# working.net
KiCad netlist of a schematic drawn in EAGLE
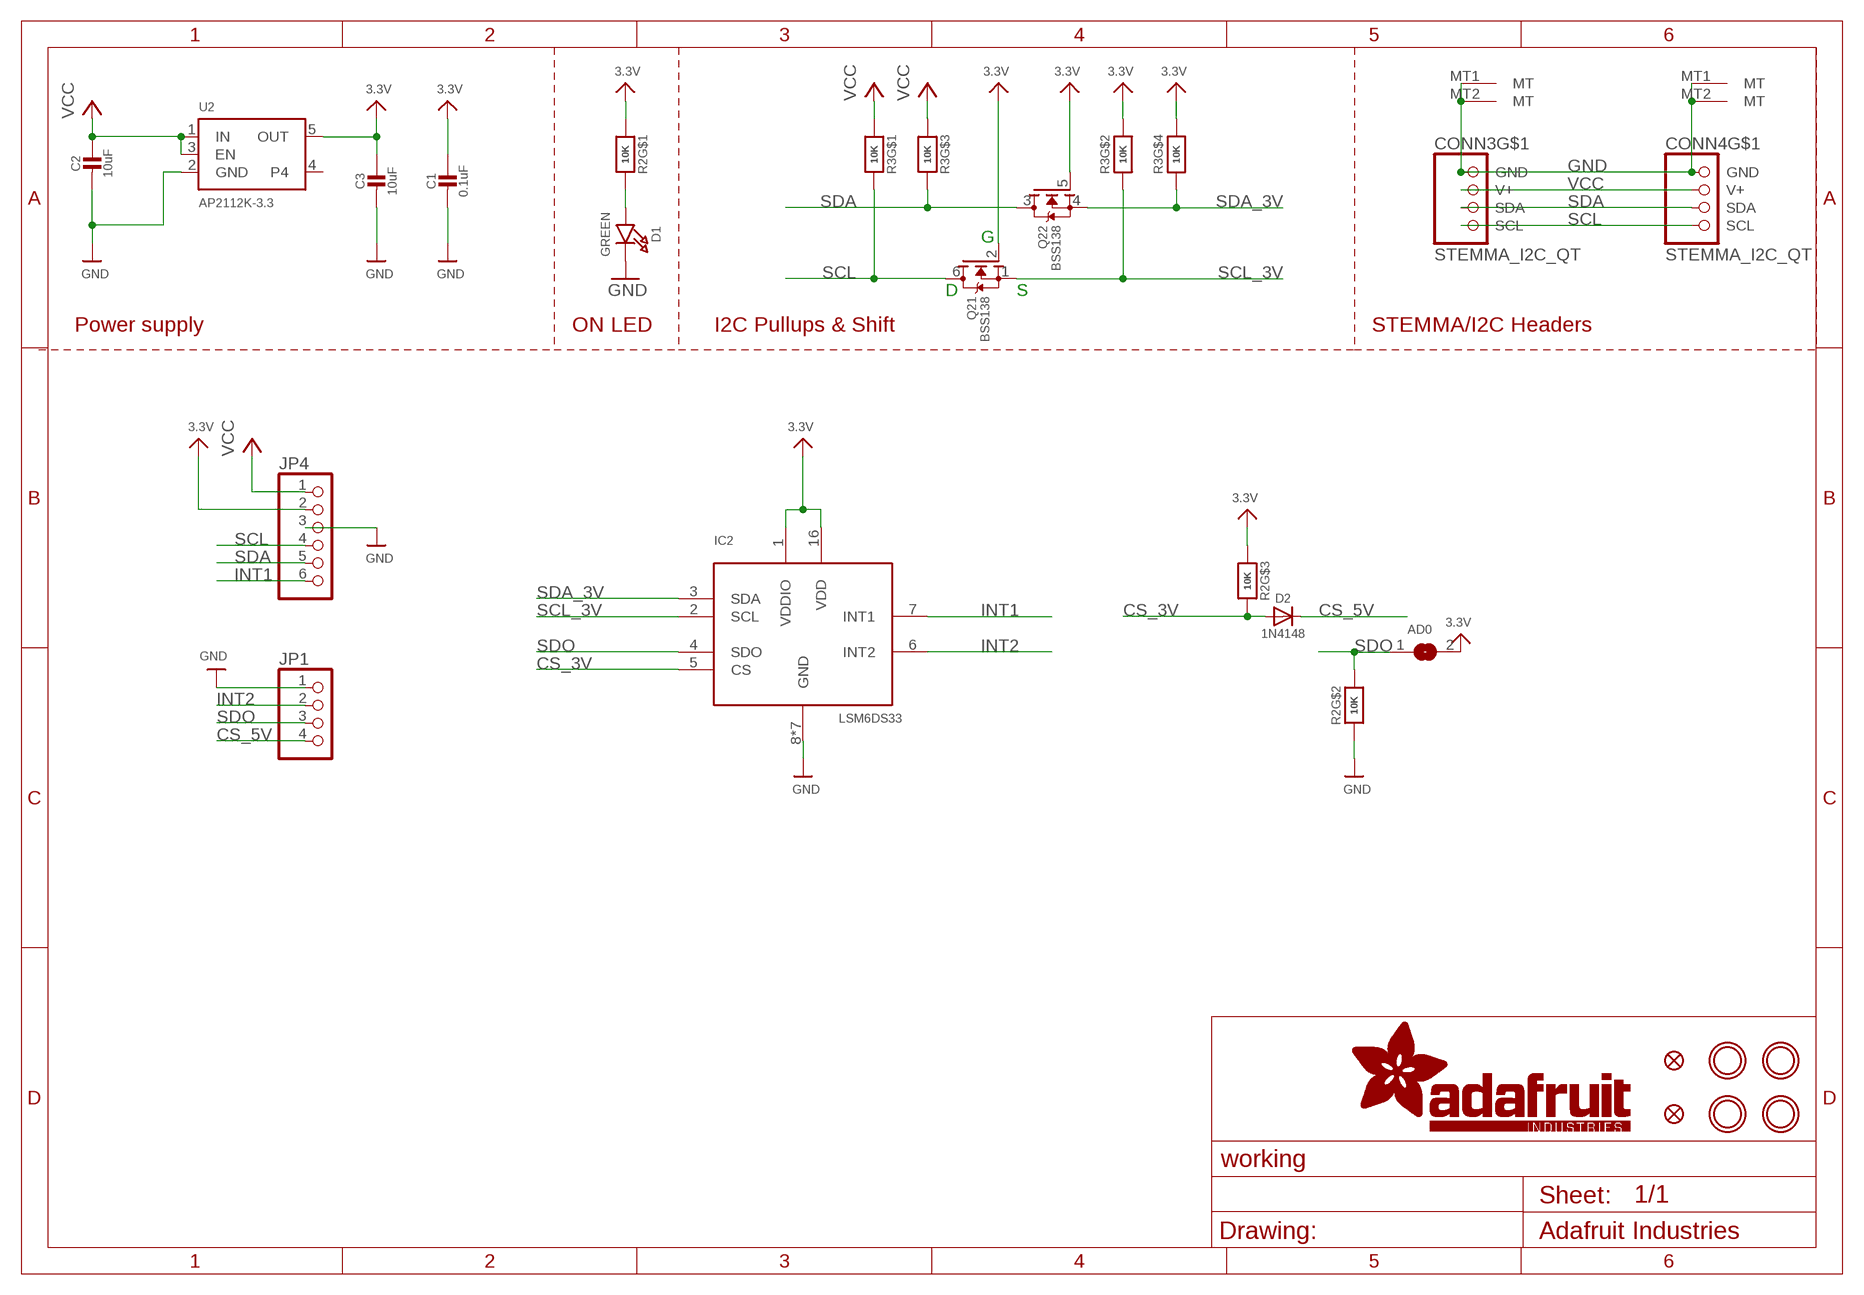
[diagram p0: schematic, sheet 1]

(export (version "E")
  (design (tool "Eeschema 10.0.6"))
  (components
    (comp (ref "AD0")
      (value "SOLDERJUMPER")
      (footprint "eagle-import:SOLDERJUMPER_ARROW_NOPASTE")
      (libsource (lib "eagle-import") (part "SOLDERJUMPER"))
    )
    (comp (ref "C1")
      (value "0.1uF")
      (footprint "eagle-import:0603-NO")
      (libsource (lib "eagle-import") (part "CAP_CERAMIC0603_NO"))
    )
    (comp (ref "C2")
      (value "10uF")
      (footprint "eagle-import:0805-NO")
      (libsource (lib "eagle-import") (part "CAP_CERAMIC0805-NOOUTLINE"))
    )
    (comp (ref "C3")
      (value "10uF")
      (footprint "eagle-import:0805-NO")
      (libsource (lib "eagle-import") (part "CAP_CERAMIC0805-NOOUTLINE"))
    )
    (comp (ref "CONN3")
      (value "STEMMA_I2C_QT")
      (footprint "eagle-import:JST_SH4")
      (libsource (lib "eagle-import") (part "STEMMA_I2C_QT"))
    )
    (comp (ref "CONN4")
      (value "STEMMA_I2C_QT")
      (footprint "eagle-import:JST_SH4")
      (libsource (lib "eagle-import") (part "STEMMA_I2C_QT"))
    )
    (comp (ref "D1")
      (value "GREEN")
      (footprint "eagle-import:CHIPLED_0603_NOOUTLINE")
      (libsource (lib "eagle-import") (part "LED0603_NOOUTLINE"))
    )
    (comp (ref "D2")
      (value "1N4148")
      (footprint "eagle-import:SOD-323")
      (libsource (lib "eagle-import") (part "DIODESOD-323"))
    )
    (comp (ref "FID3")
      (value "FIDUCIAL_1MM")
      (footprint "eagle-import:FIDUCIAL_1MM")
      (libsource (lib "eagle-import") (part "FIDUCIAL_1MM"))
    )
    (comp (ref "FID4")
      (value "FIDUCIAL_1MM")
      (footprint "eagle-import:FIDUCIAL_1MM")
      (libsource (lib "eagle-import") (part "FIDUCIAL_1MM"))
    )
    (comp (ref "IC2")
      (value "LSM6DS33")
      (footprint "eagle-import:LGA16_3X3MM")
      (libsource (lib "eagle-import") (part "LSM6DS33"))
    )
    (comp (ref "JP1")
      (value "HEADER-1X4ROUND")
      (footprint "eagle-import:1X04_ROUND")
      (libsource (lib "eagle-import") (part "HEADER-1X4ROUND"))
    )
    (comp (ref "JP4")
      (value "HEADER-1X670MIL")
      (footprint "eagle-import:1X06_ROUND_70")
      (libsource (lib "eagle-import") (part "HEADER-1X670MIL"))
    )
    (comp (ref "Q2")
      (value "BSS138")
      (footprint "eagle-import:SOT363")
      (libsource (lib "eagle-import") (part "MOSFET-N_DUAL"))
    )
    (comp (ref "R2")
      (value "10K")
      (footprint "eagle-import:RESPACK_4X0603")
      (libsource (lib "eagle-import") (part "RESISTOR_4PACK"))
    )
    (comp (ref "R3")
      (value "10K")
      (footprint "eagle-import:RESPACK_4X0603")
      (libsource (lib "eagle-import") (part "RESISTOR_4PACK"))
    )
    (comp (ref "U$1")
      (value "MOUNTINGHOLE2.5")
      (footprint "eagle-import:MOUNTINGHOLE_2.5_PLATED")
      (libsource (lib "eagle-import") (part "MOUNTINGHOLE2.5"))
    )
    (comp (ref "U$17")
      (value "MOUNTINGHOLE2.5")
      (footprint "eagle-import:MOUNTINGHOLE_2.5_PLATED")
      (libsource (lib "eagle-import") (part "MOUNTINGHOLE2.5"))
    )
    (comp (ref "U$19")
      (value "MOUNTINGHOLE2.5")
      (footprint "eagle-import:MOUNTINGHOLE_2.5_PLATED")
      (libsource (lib "eagle-import") (part "MOUNTINGHOLE2.5"))
    )
    (comp (ref "U$21")
      (value "MOUNTINGHOLE2.5")
      (footprint "eagle-import:MOUNTINGHOLE_2.5_PLATED")
      (libsource (lib "eagle-import") (part "MOUNTINGHOLE2.5"))
    )
    (comp (ref "U2")
      (value "AP2112K-3.3")
      (footprint "eagle-import:SOT23-5")
      (libsource (lib "eagle-import") (part "VREG_SOT23-5"))
    )
  )
  (nets
    (net (code "1") (name "/CS_3V") (class "Default")
      (node (ref "D2") (pin "A") (pinfunction "A_A") (pintype "passive"))
      (node (ref "IC2") (pin "5") (pinfunction "CS_5") (pintype "input"))
      (node (ref "R2") (pin "6") (pinfunction "2_6") (pintype "passive"))
    )
    (net (code "2") (name "/CS_5V") (class "Default")
      (node (ref "D2") (pin "C") (pinfunction "C_C") (pintype "passive"))
      (node (ref "JP1") (pin "4") (pinfunction "4_4") (pintype "passive"))
    )
    (net (code "3") (name "/INT1") (class "Default")
      (node (ref "IC2") (pin "7") (pinfunction "INT1_7") (pintype "output"))
      (node (ref "JP4") (pin "6") (pinfunction "6_6") (pintype "passive"))
    )
    (net (code "4") (name "/INT2") (class "Default")
      (node (ref "IC2") (pin "6") (pinfunction "INT2_6") (pintype "output"))
      (node (ref "JP1") (pin "2") (pinfunction "2_2") (pintype "passive"))
    )
    (net (code "5") (name "/SCL") (class "Default")
      (node (ref "CONN3") (pin "4") (pinfunction "SCL_4") (pintype "passive"))
      (node (ref "CONN4") (pin "4") (pinfunction "SCL_4") (pintype "passive"))
      (node (ref "JP4") (pin "4") (pinfunction "4_4") (pintype "passive"))
      (node (ref "Q2") (pin "6") (pinfunction "D_6") (pintype "bidirectional"))
      (node (ref "R3") (pin "8") (pinfunction "2_8") (pintype "passive"))
    )
    (net (code "6") (name "/SCL_3V") (class "Default")
      (node (ref "IC2") (pin "2") (pinfunction "SCL_2") (pintype "bidirectional"))
      (node (ref "Q2") (pin "1") (pinfunction "S_1") (pintype "bidirectional"))
      (node (ref "R3") (pin "7") (pinfunction "2_7") (pintype "passive"))
    )
    (net (code "7") (name "/SDA") (class "Default")
      (node (ref "CONN3") (pin "3") (pinfunction "SDA_3") (pintype "passive"))
      (node (ref "CONN4") (pin "3") (pinfunction "SDA_3") (pintype "passive"))
      (node (ref "JP4") (pin "5") (pinfunction "5_5") (pintype "passive"))
      (node (ref "Q2") (pin "3") (pinfunction "D_3") (pintype "bidirectional"))
      (node (ref "R3") (pin "6") (pinfunction "2_6") (pintype "passive"))
    )
    (net (code "8") (name "/SDA_3V") (class "Default")
      (node (ref "IC2") (pin "3") (pinfunction "SDA_3") (pintype "bidirectional"))
      (node (ref "Q2") (pin "4") (pinfunction "S_4") (pintype "bidirectional"))
      (node (ref "R3") (pin "5") (pinfunction "2_5") (pintype "passive"))
    )
    (net (code "9") (name "/SDO") (class "Default")
      (node (ref "AD0") (pin "1") (pinfunction "1_1") (pintype "passive"))
      (node (ref "IC2") (pin "4") (pinfunction "SDO_4") (pintype "bidirectional"))
      (node (ref "JP1") (pin "3") (pinfunction "3_3") (pintype "passive"))
      (node (ref "R2") (pin "7") (pinfunction "2_7") (pintype "passive"))
    )
    (net (code "10") (name "3.3V") (class "Default")
      (node (ref "AD0") (pin "2") (pinfunction "2_2") (pintype "passive"))
      (node (ref "C1") (pin "1") (pinfunction "1_1") (pintype "passive"))
      (node (ref "C3") (pin "1") (pinfunction "1_1") (pintype "passive"))
      (node (ref "IC2") (pin "1") (pinfunction "VDDIO_1") (pintype "power_in"))
      (node (ref "IC2") (pin "16") (pinfunction "VDD_16") (pintype "power_in"))
      (node (ref "JP4") (pin "2") (pinfunction "2_2") (pintype "passive"))
      (node (ref "Q2") (pin "2") (pinfunction "G_2") (pintype "bidirectional"))
      (node (ref "Q2") (pin "5") (pinfunction "G_5") (pintype "bidirectional"))
      (node (ref "R2") (pin "1") (pinfunction "1_1") (pintype "passive"))
      (node (ref "R2") (pin "3") (pinfunction "1_3") (pintype "passive"))
      (node (ref "R3") (pin "2") (pinfunction "1_2") (pintype "passive"))
      (node (ref "R3") (pin "4") (pinfunction "1_4") (pintype "passive"))
      (node (ref "U2") (pin "5") (pinfunction "OUT_5") (pintype "power_in"))
    )
    (net (code "11") (name "GND") (class "Default")
      (node (ref "C1") (pin "2") (pinfunction "2_2") (pintype "passive"))
      (node (ref "C2") (pin "2") (pinfunction "2_2") (pintype "passive"))
      (node (ref "C3") (pin "2") (pinfunction "2_2") (pintype "passive"))
      (node (ref "CONN3") (pin "1") (pinfunction "GND_1") (pintype "passive"))
      (node (ref "CONN3") (pin "MT1") (pinfunction "MT_MT1") (pintype "bidirectional"))
      (node (ref "CONN3") (pin "MT2") (pinfunction "MT_MT2") (pintype "bidirectional"))
      (node (ref "CONN4") (pin "1") (pinfunction "GND_1") (pintype "passive"))
      (node (ref "CONN4") (pin "MT1") (pinfunction "MT_MT1") (pintype "bidirectional"))
      (node (ref "CONN4") (pin "MT2") (pinfunction "MT_MT2") (pintype "bidirectional"))
      (node (ref "D1") (pin "C") (pinfunction "C_C") (pintype "passive"))
      (node (ref "IC2") (pin "10") (pinfunction "GND_10") (pintype "power_in"))
      (node (ref "IC2") (pin "11") (pinfunction "GND_11") (pintype "power_in"))
      (node (ref "IC2") (pin "12") (pinfunction "GND_12") (pintype "power_in"))
      (node (ref "IC2") (pin "13") (pinfunction "GND_13") (pintype "power_in"))
      (node (ref "IC2") (pin "15") (pinfunction "GND_15") (pintype "power_in"))
      (node (ref "IC2") (pin "8") (pinfunction "GND_8") (pintype "power_in"))
      (node (ref "IC2") (pin "9") (pinfunction "GND_9") (pintype "power_in"))
      (node (ref "JP1") (pin "1") (pinfunction "1_1") (pintype "passive"))
      (node (ref "JP4") (pin "3") (pinfunction "3_3") (pintype "passive"))
      (node (ref "R2") (pin "2") (pinfunction "1_2") (pintype "passive"))
      (node (ref "U2") (pin "2") (pinfunction "GND_2") (pintype "power_in"))
    )
    (net (code "12") (name "Net-(R2A-2)") (class "Default")
      (node (ref "D1") (pin "A") (pinfunction "A_A") (pintype "passive"))
      (node (ref "R2") (pin "8") (pinfunction "2_8") (pintype "passive"))
    )
    (net (code "13") (name "VCC") (class "Default")
      (node (ref "C2") (pin "1") (pinfunction "1_1") (pintype "passive"))
      (node (ref "CONN3") (pin "2") (pinfunction "V+_2") (pintype "passive"))
      (node (ref "CONN4") (pin "2") (pinfunction "V+_2") (pintype "passive"))
      (node (ref "JP4") (pin "1") (pinfunction "1_1") (pintype "passive"))
      (node (ref "R3") (pin "1") (pinfunction "1_1") (pintype "passive"))
      (node (ref "R3") (pin "3") (pinfunction "1_3") (pintype "passive"))
      (node (ref "U2") (pin "1") (pinfunction "IN_1") (pintype "power_in"))
      (node (ref "U2") (pin "3") (pinfunction "EN_3") (pintype "input"))
    )
    (net (code "14") (name "unconnected-(U2-P4-Pad4)") (class "Default")
      (node (ref "U2") (pin "4") (pinfunction "P4_4") (pintype "bidirectional"))
    )
  )
)
